# Brians_test_board_1_12a.net
KiCad netlist of a schematic drawn in EAGLE
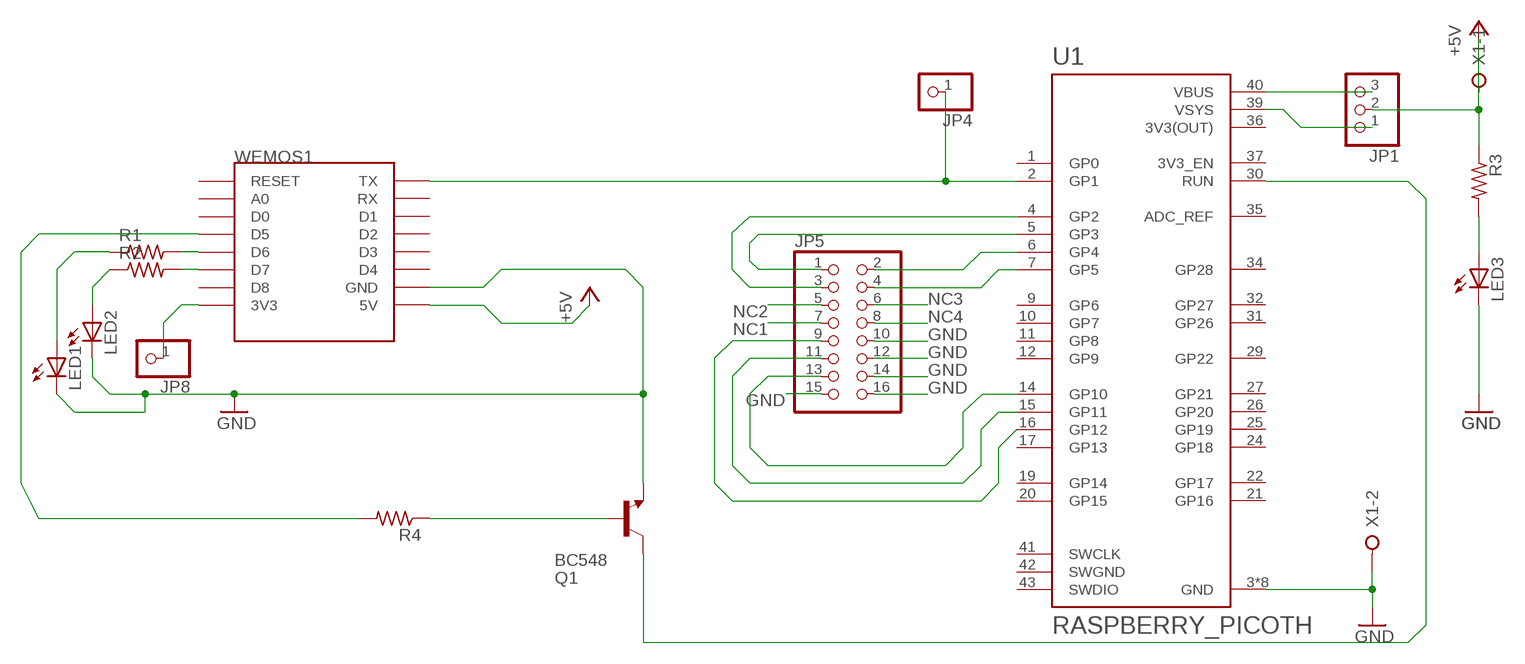
[diagram p0: schematic, sheet 1]

(export (version "E")
  (design (tool "Eeschema 10.0.6"))
  (components
    (comp (ref "JP1")
      (value "PINHD-1X3")
      (footprint "eagle-import:1X03")
      (libsource (lib "eagle-import") (part "PINHD-1X3"))
    )
    (comp (ref "JP4")
      (value "PINHD-1X1")
      (footprint "eagle-import:1X01")
      (libsource (lib "eagle-import") (part "PINHD-1X1"))
    )
    (comp (ref "JP5")
      (value "PINHD-2X8")
      (footprint "eagle-import:2X08")
      (libsource (lib "eagle-import") (part "PINHD-2X8"))
    )
    (comp (ref "JP8")
      (value "PINHD-1X1")
      (footprint "eagle-import:1X01")
      (libsource (lib "eagle-import") (part "PINHD-1X1"))
    )
    (comp (ref "LED1")
      (value "LED3MM")
      (footprint "eagle-import:LED3MM")
      (libsource (lib "eagle-import") (part "LED3MM"))
    )
    (comp (ref "LED2")
      (value "LED3MM")
      (footprint "eagle-import:LED3MM")
      (libsource (lib "eagle-import") (part "LED3MM"))
    )
    (comp (ref "LED3")
      (value "LED3MM")
      (footprint "eagle-import:LED3MM")
      (libsource (lib "eagle-import") (part "LED3MM"))
    )
    (comp (ref "Q1")
      (value "BC548")
      (footprint "eagle-import:TO92-EBC")
      (libsource (lib "eagle-import") (part "BC548"))
    )
    (comp (ref "R1")
      (value "R-US_0204/2V")
      (footprint "eagle-import:0204V")
      (libsource (lib "eagle-import") (part "R-US_0204/2V"))
    )
    (comp (ref "R2")
      (value "R-US_0204/2V")
      (footprint "eagle-import:0204V")
      (libsource (lib "eagle-import") (part "R-US_0204/2V"))
    )
    (comp (ref "R3")
      (value "R-US_0207/10")
      (footprint "eagle-import:0207_10")
      (libsource (lib "eagle-import") (part "R-US_0207/10"))
    )
    (comp (ref "R4")
      (value "R-US_0204/2V")
      (footprint "eagle-import:0204V")
      (libsource (lib "eagle-import") (part "R-US_0204/2V"))
    )
    (comp (ref "U1")
      (value "RASPBERRY_PICOTH")
      (footprint "eagle-import:PICO-PKG-TH")
      (libsource (lib "eagle-import") (part "RASPBERRY_PICOTH"))
    )
    (comp (ref "WEMOS1")
      (value "WEMOS-D1-MINI")
      (footprint "eagle-import:WEMOS-D1-MINI")
      (libsource (lib "eagle-import") (part "WEMOS-D1-MINI"))
    )
    (comp (ref "X1")
      (value "W237-02P")
      (footprint "eagle-import:W237-132")
      (libsource (lib "eagle-import") (part "W237-02P"))
    )
  )
  (nets
    (net (code "1") (name "+5V") (class "Default")
      (node (ref "JP1") (pin "2") (pinfunction "2_2") (pintype "passive"))
      (node (ref "R3") (pin "1") (pinfunction "1_1") (pintype "passive"))
      (node (ref "WEMOS1") (pin "5V") (pinfunction "5V_5V") (pintype "bidirectional"))
      (node (ref "X1") (pin "1") (pinfunction "KL_1") (pintype "passive"))
    )
    (net (code "2") (name "/3V3(OUT)") (class "Default")
      (node (ref "U1") (pin "36") (pinfunction "3V3(OUT)_36") (pintype "power_in"))
    )
    (net (code "3") (name "/NC1") (class "Default")
      (node (ref "JP5") (pin "7") (pinfunction "7_7") (pintype "passive"))
    )
    (net (code "4") (name "/NC2") (class "Default")
      (node (ref "JP5") (pin "5") (pinfunction "5_5") (pintype "passive"))
    )
    (net (code "5") (name "/NC3") (class "Default")
      (node (ref "JP5") (pin "6") (pinfunction "6_6") (pintype "passive"))
    )
    (net (code "6") (name "/NC4") (class "Default")
      (node (ref "JP5") (pin "8") (pinfunction "8_8") (pintype "passive"))
    )
    (net (code "7") (name "/SWGND") (class "Default")
      (node (ref "U1") (pin "42") (pinfunction "SWGND_42") (pintype "power_in"))
    )
    (net (code "8") (name "GND") (class "Default")
      (node (ref "JP5") (pin "10") (pinfunction "10_10") (pintype "passive"))
      (node (ref "JP5") (pin "12") (pinfunction "12_12") (pintype "passive"))
      (node (ref "JP5") (pin "14") (pinfunction "14_14") (pintype "passive"))
      (node (ref "JP5") (pin "15") (pinfunction "15_15") (pintype "passive"))
      (node (ref "JP5") (pin "16") (pinfunction "16_16") (pintype "passive"))
      (node (ref "LED1") (pin "K") (pinfunction "C_K") (pintype "passive"))
      (node (ref "LED2") (pin "K") (pinfunction "C_K") (pintype "passive"))
      (node (ref "LED3") (pin "K") (pinfunction "C_K") (pintype "passive"))
      (node (ref "Q1") (pin "E") (pinfunction "E_E") (pintype "passive"))
      (node (ref "U1") (pin "13") (pinfunction "GND_13") (pintype "power_in"))
      (node (ref "U1") (pin "18") (pinfunction "GND_18") (pintype "power_in"))
      (node (ref "U1") (pin "23") (pinfunction "GND_23") (pintype "power_in"))
      (node (ref "U1") (pin "28") (pinfunction "GND_28") (pintype "power_in"))
      (node (ref "U1") (pin "3") (pinfunction "GND_3") (pintype "power_in"))
      (node (ref "U1") (pin "33") (pinfunction "GND_33") (pintype "power_in"))
      (node (ref "U1") (pin "38") (pinfunction "GND_38") (pintype "power_in"))
      (node (ref "U1") (pin "8") (pinfunction "GND_8") (pintype "power_in"))
      (node (ref "WEMOS1") (pin "GND") (pinfunction "GND_GND") (pintype "bidirectional"))
      (node (ref "X1") (pin "2") (pinfunction "KL_2") (pintype "passive"))
    )
    (net (code "9") (name "Net-(JP8-Pad1)") (class "Default")
      (node (ref "JP8") (pin "1") (pinfunction "1_1") (pintype "passive"))
      (node (ref "WEMOS1") (pin "3V3") (pinfunction "3V3_3V3") (pintype "bidirectional"))
    )
    (net (code "10") (name "Net-(LED1-PadA)") (class "Default")
      (node (ref "LED1") (pin "A") (pinfunction "A_A") (pintype "passive"))
      (node (ref "R1") (pin "1") (pinfunction "1_1") (pintype "passive"))
    )
    (net (code "11") (name "Net-(LED2-PadA)") (class "Default")
      (node (ref "LED2") (pin "A") (pinfunction "A_A") (pintype "passive"))
      (node (ref "R2") (pin "1") (pinfunction "1_1") (pintype "passive"))
    )
    (net (code "12") (name "Net-(LED3-PadA)") (class "Default")
      (node (ref "LED3") (pin "A") (pinfunction "A_A") (pintype "passive"))
      (node (ref "R3") (pin "2") (pinfunction "2_2") (pintype "passive"))
    )
    (net (code "13") (name "Net-(Q1-PadB)") (class "Default")
      (node (ref "Q1") (pin "B") (pinfunction "B_B") (pintype "passive"))
      (node (ref "R4") (pin "1") (pinfunction "1_1") (pintype "passive"))
    )
    (net (code "14") (name "Net-(R1-Pad2)") (class "Default")
      (node (ref "R1") (pin "2") (pinfunction "2_2") (pintype "passive"))
      (node (ref "WEMOS1") (pin "D6") (pinfunction "D6_D6") (pintype "bidirectional"))
    )
    (net (code "15") (name "Net-(R2-Pad2)") (class "Default")
      (node (ref "R2") (pin "2") (pinfunction "2_2") (pintype "passive"))
      (node (ref "WEMOS1") (pin "D7") (pinfunction "D7_D7") (pintype "bidirectional"))
    )
    (net (code "16") (name "Net-(R4-Pad2)") (class "Default")
      (node (ref "R4") (pin "2") (pinfunction "2_2") (pintype "passive"))
      (node (ref "WEMOS1") (pin "D5") (pinfunction "D5_D5") (pintype "bidirectional"))
    )
    (net (code "17") (name "Net-(U1-GP1)") (class "Default")
      (node (ref "JP4") (pin "1") (pinfunction "1_1") (pintype "passive"))
      (node (ref "U1") (pin "2") (pinfunction "GP1_2") (pintype "bidirectional"))
      (node (ref "WEMOS1") (pin "TX") (pinfunction "TX_TX") (pintype "bidirectional"))
    )
    (net (code "18") (name "Net-(U1-GP2)") (class "Default")
      (node (ref "JP5") (pin "3") (pinfunction "3_3") (pintype "passive"))
      (node (ref "U1") (pin "4") (pinfunction "GP2_4") (pintype "bidirectional"))
    )
    (net (code "19") (name "Net-(U1-GP3)") (class "Default")
      (node (ref "JP5") (pin "1") (pinfunction "1_1") (pintype "passive"))
      (node (ref "U1") (pin "5") (pinfunction "GP3_5") (pintype "bidirectional"))
    )
    (net (code "20") (name "Net-(U1-GP4)") (class "Default")
      (node (ref "JP5") (pin "2") (pinfunction "2_2") (pintype "passive"))
      (node (ref "U1") (pin "6") (pinfunction "GP4_6") (pintype "bidirectional"))
    )
    (net (code "21") (name "Net-(U1-GP5)") (class "Default")
      (node (ref "JP5") (pin "4") (pinfunction "4_4") (pintype "passive"))
      (node (ref "U1") (pin "7") (pinfunction "GP5_7") (pintype "bidirectional"))
    )
    (net (code "22") (name "Net-(U1-GP10)") (class "Default")
      (node (ref "JP5") (pin "13") (pinfunction "13_13") (pintype "passive"))
      (node (ref "U1") (pin "14") (pinfunction "GP10_14") (pintype "bidirectional"))
    )
    (net (code "23") (name "Net-(U1-GP11)") (class "Default")
      (node (ref "JP5") (pin "11") (pinfunction "11_11") (pintype "passive"))
      (node (ref "U1") (pin "15") (pinfunction "GP11_15") (pintype "bidirectional"))
    )
    (net (code "24") (name "Net-(U1-GP12)") (class "Default")
      (node (ref "JP5") (pin "9") (pinfunction "9_9") (pintype "passive"))
      (node (ref "U1") (pin "16") (pinfunction "GP12_16") (pintype "bidirectional"))
    )
    (net (code "25") (name "Net-(U1-RUN)") (class "Default")
      (node (ref "Q1") (pin "C") (pinfunction "C_C") (pintype "passive"))
      (node (ref "U1") (pin "30") (pinfunction "RUN_30") (pintype "input"))
    )
    (net (code "26") (name "Net-(U1-VBUS)") (class "Default")
      (node (ref "JP1") (pin "3") (pinfunction "3_3") (pintype "passive"))
      (node (ref "U1") (pin "40") (pinfunction "VBUS_40") (pintype "power_in"))
    )
    (net (code "27") (name "Net-(U1-VSYS)") (class "Default")
      (node (ref "JP1") (pin "1") (pinfunction "1_1") (pintype "passive"))
      (node (ref "U1") (pin "39") (pinfunction "VSYS_39") (pintype "power_in"))
    )
    (net (code "28") (name "unconnected-(U1-3V3_EN-Pad37)") (class "Default")
      (node (ref "U1") (pin "37") (pinfunction "3V3_EN_37") (pintype "input"))
    )
    (net (code "29") (name "unconnected-(U1-ADC_REF-Pad35)") (class "Default")
      (node (ref "U1") (pin "35") (pinfunction "ADC_REF_35") (pintype "input"))
    )
    (net (code "30") (name "unconnected-(U1-GP0-Pad1)") (class "Default")
      (node (ref "U1") (pin "1") (pinfunction "GP0_1") (pintype "bidirectional"))
    )
    (net (code "31") (name "unconnected-(U1-GP6-Pad9)") (class "Default")
      (node (ref "U1") (pin "9") (pinfunction "GP6_9") (pintype "bidirectional"))
    )
    (net (code "32") (name "unconnected-(U1-GP7-Pad10)") (class "Default")
      (node (ref "U1") (pin "10") (pinfunction "GP7_10") (pintype "bidirectional"))
    )
    (net (code "33") (name "unconnected-(U1-GP8-Pad11)") (class "Default")
      (node (ref "U1") (pin "11") (pinfunction "GP8_11") (pintype "bidirectional"))
    )
    (net (code "34") (name "unconnected-(U1-GP9-Pad12)") (class "Default")
      (node (ref "U1") (pin "12") (pinfunction "GP9_12") (pintype "bidirectional"))
    )
    (net (code "35") (name "unconnected-(U1-GP13-Pad17)") (class "Default")
      (node (ref "U1") (pin "17") (pinfunction "GP13_17") (pintype "bidirectional"))
    )
    (net (code "36") (name "unconnected-(U1-GP14-Pad19)") (class "Default")
      (node (ref "U1") (pin "19") (pinfunction "GP14_19") (pintype "bidirectional"))
    )
    (net (code "37") (name "unconnected-(U1-GP15-Pad20)") (class "Default")
      (node (ref "U1") (pin "20") (pinfunction "GP15_20") (pintype "bidirectional"))
    )
    (net (code "38") (name "unconnected-(U1-GP16-Pad21)") (class "Default")
      (node (ref "U1") (pin "21") (pinfunction "GP16_21") (pintype "bidirectional"))
    )
    (net (code "39") (name "unconnected-(U1-GP17-Pad22)") (class "Default")
      (node (ref "U1") (pin "22") (pinfunction "GP17_22") (pintype "bidirectional"))
    )
    (net (code "40") (name "unconnected-(U1-GP18-Pad24)") (class "Default")
      (node (ref "U1") (pin "24") (pinfunction "GP18_24") (pintype "bidirectional"))
    )
    (net (code "41") (name "unconnected-(U1-GP19-Pad25)") (class "Default")
      (node (ref "U1") (pin "25") (pinfunction "GP19_25") (pintype "bidirectional"))
    )
    (net (code "42") (name "unconnected-(U1-GP20-Pad26)") (class "Default")
      (node (ref "U1") (pin "26") (pinfunction "GP20_26") (pintype "bidirectional"))
    )
    (net (code "43") (name "unconnected-(U1-GP21-Pad27)") (class "Default")
      (node (ref "U1") (pin "27") (pinfunction "GP21_27") (pintype "bidirectional"))
    )
    (net (code "44") (name "unconnected-(U1-GP22-Pad29)") (class "Default")
      (node (ref "U1") (pin "29") (pinfunction "GP22_29") (pintype "bidirectional"))
    )
    (net (code "45") (name "unconnected-(U1-GP26-Pad31)") (class "Default")
      (node (ref "U1") (pin "31") (pinfunction "GP26_31") (pintype "bidirectional"))
    )
    (net (code "46") (name "unconnected-(U1-GP27-Pad32)") (class "Default")
      (node (ref "U1") (pin "32") (pinfunction "GP27_32") (pintype "bidirectional"))
    )
    (net (code "47") (name "unconnected-(U1-GP28-Pad34)") (class "Default")
      (node (ref "U1") (pin "34") (pinfunction "GP28_34") (pintype "bidirectional"))
    )
    (net (code "48") (name "unconnected-(U1-SWCLK-Pad41)") (class "Default")
      (node (ref "U1") (pin "41") (pinfunction "SWCLK_41") (pintype "input"))
    )
    (net (code "49") (name "unconnected-(U1-SWDIO-Pad43)") (class "Default")
      (node (ref "U1") (pin "43") (pinfunction "SWDIO_43") (pintype "bidirectional"))
    )
    (net (code "50") (name "unconnected-(WEMOS1-PadA0)") (class "Default")
      (node (ref "WEMOS1") (pin "A0") (pinfunction "A0_A0") (pintype "bidirectional"))
    )
    (net (code "51") (name "unconnected-(WEMOS1-PadD0)") (class "Default")
      (node (ref "WEMOS1") (pin "D0") (pinfunction "D0_D0") (pintype "bidirectional"))
    )
    (net (code "52") (name "unconnected-(WEMOS1-PadD1)") (class "Default")
      (node (ref "WEMOS1") (pin "D1") (pinfunction "D1_D1") (pintype "bidirectional"))
    )
    (net (code "53") (name "unconnected-(WEMOS1-PadD2)") (class "Default")
      (node (ref "WEMOS1") (pin "D2") (pinfunction "D2_D2") (pintype "bidirectional"))
    )
    (net (code "54") (name "unconnected-(WEMOS1-PadD3)") (class "Default")
      (node (ref "WEMOS1") (pin "D3") (pinfunction "D3_D3") (pintype "bidirectional"))
    )
    (net (code "55") (name "unconnected-(WEMOS1-PadD4)") (class "Default")
      (node (ref "WEMOS1") (pin "D4") (pinfunction "D4_D4") (pintype "bidirectional"))
    )
    (net (code "56") (name "unconnected-(WEMOS1-PadD8)") (class "Default")
      (node (ref "WEMOS1") (pin "D8") (pinfunction "D8_D8") (pintype "bidirectional"))
    )
    (net (code "57") (name "unconnected-(WEMOS1-PadRESET)") (class "Default")
      (node (ref "WEMOS1") (pin "RESET") (pinfunction "RESET_RESET") (pintype "bidirectional"))
    )
    (net (code "58") (name "unconnected-(WEMOS1-PadRX)") (class "Default")
      (node (ref "WEMOS1") (pin "RX") (pinfunction "RX_RX") (pintype "bidirectional"))
    )
  )
)
